# SparkFun_Qwiic_PIR.net
KiCad netlist of a schematic drawn in EAGLE
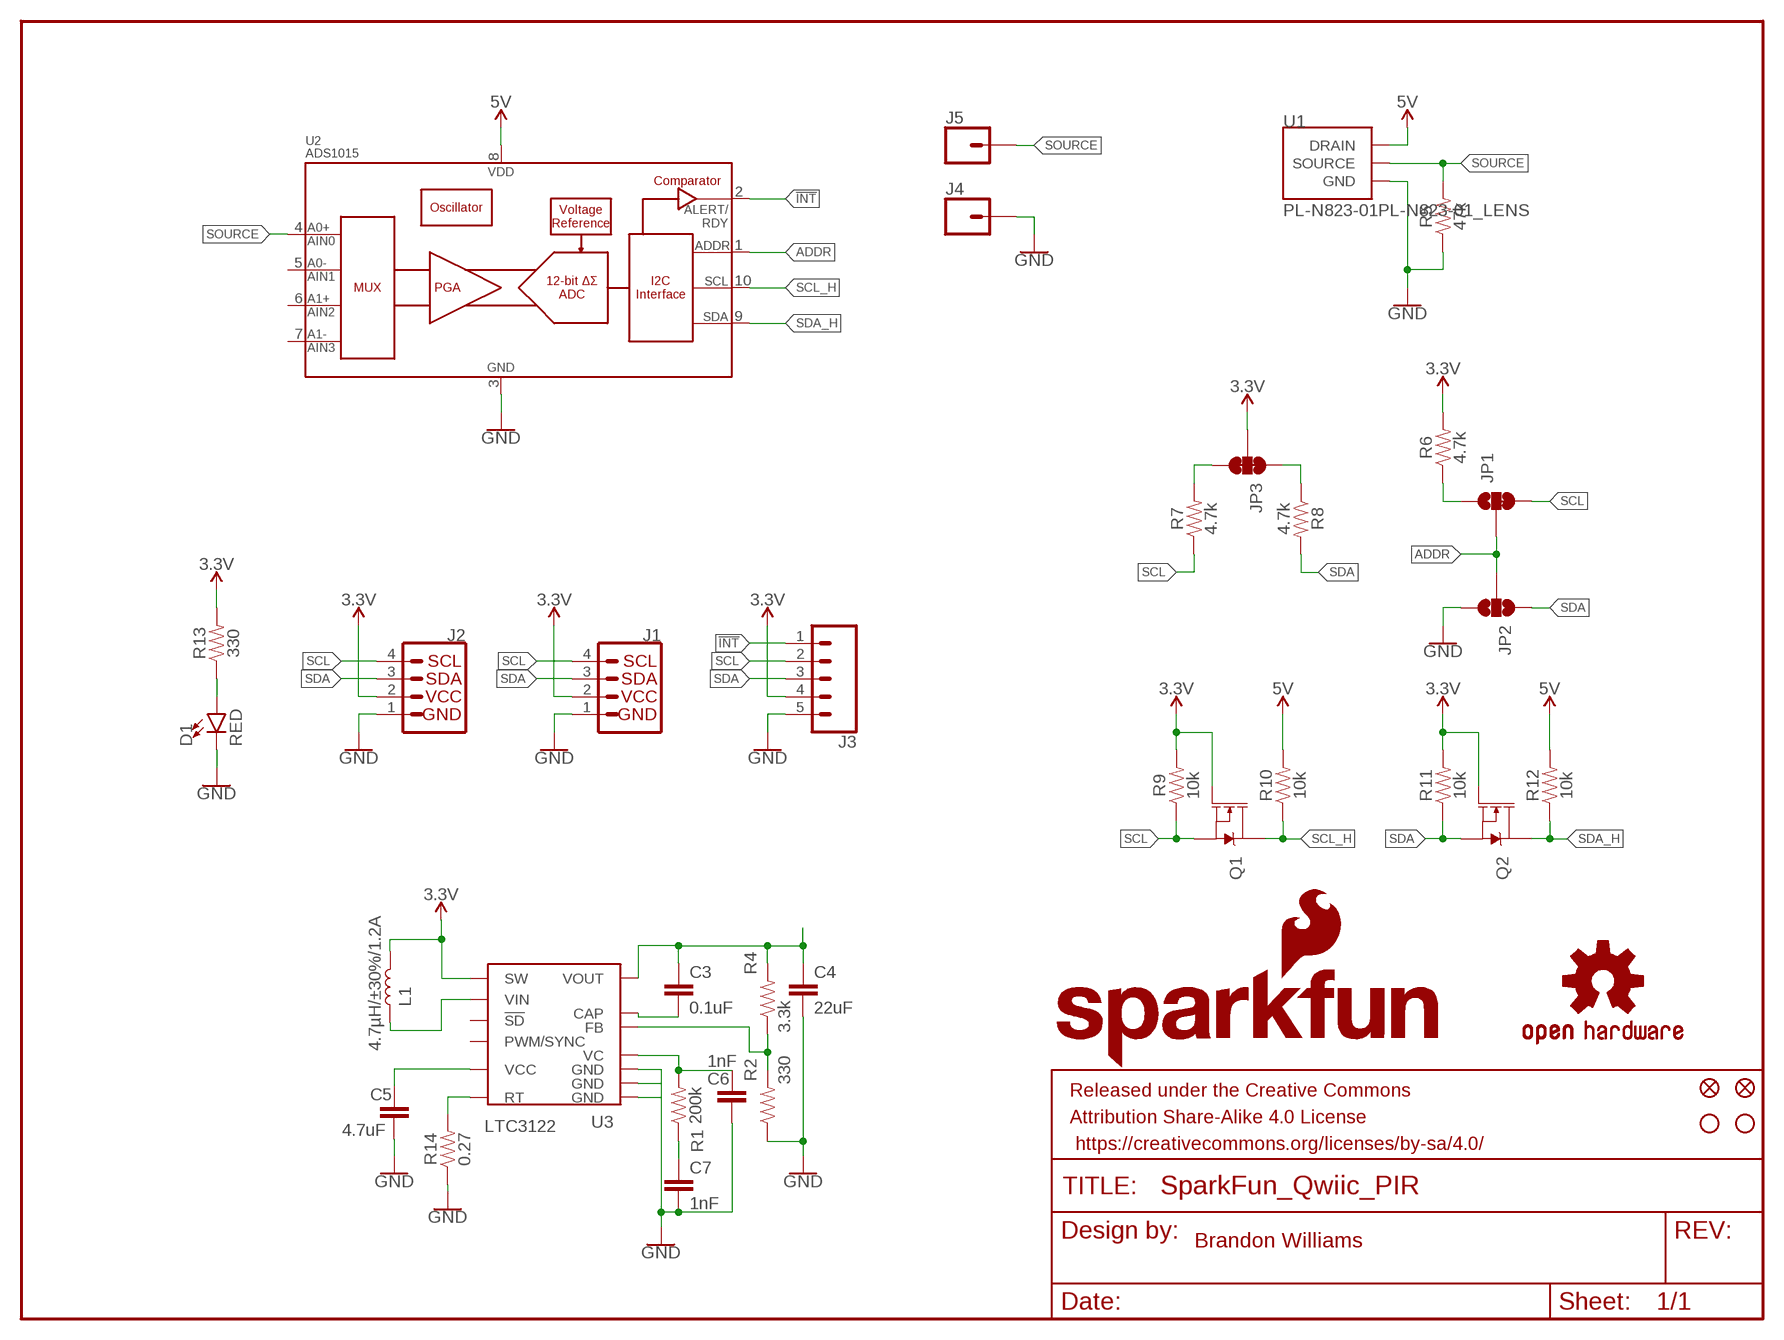
[diagram p0: schematic, sheet 1]

(export (version "E")
  (design (tool "Eeschema 10.0.6"))
  (components
    (comp (ref "C3")
      (value "0.1uF")
      (footprint "eagle-import:0603")
      (libsource (lib "eagle-import") (part "0.1UF-0603-25V-(+80/-20%)"))
    )
    (comp (ref "C4")
      (value "22uF")
      (footprint "eagle-import:0805")
      (libsource (lib "eagle-import") (part "22UF-0805-6.3V-20%"))
    )
    (comp (ref "C5")
      (value "4.7uF")
      (footprint "eagle-import:1206")
      (libsource (lib "eagle-import") (part "4.7UF-1206-16V-(+80/-20%)"))
    )
    (comp (ref "C6")
      (value "1nF")
      (footprint "eagle-import:0603")
      (libsource (lib "eagle-import") (part "1.0NF/1000PF-0603-50V-10%"))
    )
    (comp (ref "C7")
      (value "1nF")
      (footprint "eagle-import:0603")
      (libsource (lib "eagle-import") (part "1.0NF/1000PF-0603-50V-10%"))
    )
    (comp (ref "D1")
      (value "RED")
      (footprint "eagle-import:LED-0603")
      (libsource (lib "eagle-import") (part "LED-RED0603"))
    )
    (comp (ref "FD1")
      (value "FIDUCIAL0.2MM")
      (footprint "eagle-import:FIDUCIAL-0.2MM")
      (libsource (lib "eagle-import") (part "FIDUCIAL0.2MM"))
    )
    (comp (ref "FD2")
      (value "FIDUCIAL0.2MM")
      (footprint "eagle-import:FIDUCIAL-0.2MM")
      (libsource (lib "eagle-import") (part "FIDUCIAL0.2MM"))
    )
    (comp (ref "FRAME1")
      (value "FRAME-LETTERNO_PACKAGE")
      (footprint "eagle-import:DUMMY")
      (fields (field (name "DESIGNER") "Nobody"))
      (libsource (lib "eagle-import") (part "FRAME-LETTERNO_PACKAGE"))
    )
    (comp (ref "H1")
      (value "STAND-OFFTIGHT")
      (footprint "eagle-import:STAND-OFF-TIGHT")
      (libsource (lib "eagle-import") (part "STAND-OFFTIGHT"))
    )
    (comp (ref "H2")
      (value "STAND-OFFTIGHT")
      (footprint "eagle-import:STAND-OFF-TIGHT")
      (libsource (lib "eagle-import") (part "STAND-OFFTIGHT"))
    )
    (comp (ref "J1")
      (value "QWIIC_RIGHT_ANGLE")
      (footprint "eagle-import:JST04_1MM_RA")
      (libsource (lib "eagle-import") (part "QWIIC_CONNECTORJS-1MM"))
    )
    (comp (ref "J2")
      (value "QWIIC_RIGHT_ANGLE")
      (footprint "eagle-import:JST04_1MM_RA")
      (libsource (lib "eagle-import") (part "QWIIC_CONNECTORJS-1MM"))
    )
    (comp (ref "J3")
      (value "CONN_05NO_SILK")
      (footprint "eagle-import:1X05_NO_SILK")
      (libsource (lib "eagle-import") (part "CONN_05NO_SILK"))
    )
    (comp (ref "J4")
      (value "CONN_01PTH_NO_SILK_YES_STOP")
      (footprint "eagle-import:1X01_NO_SILK")
      (libsource (lib "eagle-import") (part "CONN_01PTH_NO_SILK_YES_STOP"))
    )
    (comp (ref "J5")
      (value "CONN_01PTH_NO_SILK_YES_STOP")
      (footprint "eagle-import:1X01_NO_SILK")
      (libsource (lib "eagle-import") (part "CONN_01PTH_NO_SILK_YES_STOP"))
    )
    (comp (ref "JP1")
      (value "JUMPER-SMT_3_1-NC_TRACE_SILK")
      (footprint "eagle-import:SMT-JUMPER_3_1-NC_TRACE_SILK")
      (libsource (lib "eagle-import") (part "JUMPER-SMT_3_1-NC_TRACE_SILK"))
    )
    (comp (ref "JP2")
      (value "JUMPER-SMT_3_NO_SILK")
      (footprint "eagle-import:SMT-JUMPER_3_NO_SILK")
      (libsource (lib "eagle-import") (part "JUMPER-SMT_3_NO_SILK"))
    )
    (comp (ref "JP3")
      (value "JUMPER-SMT_3_2-NC_TRACE_SILK")
      (footprint "eagle-import:SMT-JUMPER_3_2-NC_TRACE_SILK")
      (libsource (lib "eagle-import") (part "JUMPER-SMT_3_2-NC_TRACE_SILK"))
    )
    (comp (ref "L1")
      (value "4.7µH/±30%/1.2A")
      (footprint "eagle-import:INDUCTOR_4.7UH")
      (libsource (lib "eagle-import") (part "INDUCTOR-CDRH-4.7UH"))
    )
    (comp (ref "LOGO1")
      (value "OSHW-LOGOMINI")
      (footprint "eagle-import:OSHW-LOGO-MINI")
      (libsource (lib "eagle-import") (part "OSHW-LOGOMINI"))
    )
    (comp (ref "LOGO3")
      (value "SFE_LOGO_NAME_FLAME.2_INCH")
      (footprint "eagle-import:SFE_LOGO_NAME_FLAME_.2")
      (libsource (lib "eagle-import") (part "SFE_LOGO_NAME_FLAME.2_INCH"))
    )
    (comp (ref "Q1")
      (value "220mA/50V/3.5Ω")
      (footprint "eagle-import:SOT23-3")
      (libsource (lib "eagle-import") (part "MOSFET-NCH-BSS138"))
    )
    (comp (ref "Q2")
      (value "220mA/50V/3.5Ω")
      (footprint "eagle-import:SOT23-3")
      (libsource (lib "eagle-import") (part "MOSFET-NCH-BSS138"))
    )
    (comp (ref "R1")
      (value "200k")
      (footprint "eagle-import:0603")
      (libsource (lib "eagle-import") (part "200KOHM-0603-1/10W-1%"))
    )
    (comp (ref "R2")
      (value "330")
      (footprint "eagle-import:0603")
      (libsource (lib "eagle-import") (part "330OHM-0603-1/10W-1%"))
    )
    (comp (ref "R4")
      (value "3.3k")
      (footprint "eagle-import:0603")
      (libsource (lib "eagle-import") (part "3.3KOHM-0603-1/10W-1%"))
    )
    (comp (ref "R5")
      (value "47k")
      (footprint "eagle-import:0603")
      (libsource (lib "eagle-import") (part "47KOHM-0603-1/10W-1%"))
    )
    (comp (ref "R6")
      (value "4.7k")
      (footprint "eagle-import:0603")
      (libsource (lib "eagle-import") (part "4.7KOHM-0603-1/10W-1%"))
    )
    (comp (ref "R7")
      (value "4.7k")
      (footprint "eagle-import:0603")
      (libsource (lib "eagle-import") (part "4.7KOHM-0603-1/10W-1%"))
    )
    (comp (ref "R8")
      (value "4.7k")
      (footprint "eagle-import:0603")
      (libsource (lib "eagle-import") (part "4.7KOHM-0603-1/10W-1%"))
    )
    (comp (ref "R9")
      (value "10k")
      (footprint "eagle-import:0402-TIGHT")
      (libsource (lib "eagle-import") (part "10KOHM-0402T-1/16W-1%"))
    )
    (comp (ref "R10")
      (value "10k")
      (footprint "eagle-import:0402-TIGHT")
      (libsource (lib "eagle-import") (part "10KOHM-0402T-1/16W-1%"))
    )
    (comp (ref "R11")
      (value "10k")
      (footprint "eagle-import:0402-TIGHT")
      (libsource (lib "eagle-import") (part "10KOHM-0402T-1/16W-1%"))
    )
    (comp (ref "R12")
      (value "10k")
      (footprint "eagle-import:0402-TIGHT")
      (libsource (lib "eagle-import") (part "10KOHM-0402T-1/16W-1%"))
    )
    (comp (ref "R13")
      (value "330")
      (footprint "eagle-import:0603")
      (libsource (lib "eagle-import") (part "330OHM-0603-1/10W-1%"))
    )
    (comp (ref "R14")
      (value "0.27")
      (footprint "eagle-import:0603")
      (libsource (lib "eagle-import") (part "0.27OHM-0603-1/10W-1%"))
    )
    (comp (ref "U1")
      (value "PL-N823-01PL-N823-01_LENS")
      (footprint "eagle-import:PL-N823-01_LENS")
      (libsource (lib "eagle-import") (part "PL-N823-01PL-N823-01_LENS"))
    )
    (comp (ref "U2")
      (value "ADS1015")
      (footprint "eagle-import:MSOP10")
      (libsource (lib "eagle-import") (part "ADS1015"))
    )
    (comp (ref "U3")
      (value "LTC3122")
      (footprint "eagle-import:LTC3122EDE#PBF")
      (libsource (lib "eagle-import") (part "LTC3122"))
    )
  )
  (nets
    (net (code "1") (name "/~{INT}") (class "Default")
      (node (ref "J3") (pin "1") (pinfunction "1_1") (pintype "passive"))
      (node (ref "U2") (pin "2") (pinfunction "ALERT/RDY_2") (pintype "bidirectional"))
    )
    (net (code "2") (name "3.3V") (class "Default")
      (node (ref "J1") (pin "2") (pinfunction "2_2") (pintype "power_in"))
      (node (ref "J2") (pin "2") (pinfunction "2_2") (pintype "power_in"))
      (node (ref "J3") (pin "4") (pinfunction "4_4") (pintype "passive"))
      (node (ref "JP3") (pin "2") (pinfunction "2_2") (pintype "passive"))
      (node (ref "L1") (pin "P$2") (pinfunction "2_P$2") (pintype "passive"))
      (node (ref "Q1") (pin "1") (pinfunction "G_1") (pintype "bidirectional"))
      (node (ref "Q2") (pin "1") (pinfunction "G_1") (pintype "bidirectional"))
      (node (ref "R11") (pin "2") (pinfunction "2_2") (pintype "passive"))
      (node (ref "R13") (pin "2") (pinfunction "2_2") (pintype "passive"))
      (node (ref "R6") (pin "2") (pinfunction "2_2") (pintype "passive"))
      (node (ref "R9") (pin "2") (pinfunction "2_2") (pintype "passive"))
      (node (ref "U3") (pin "P$1") (pinfunction "SW_P$1") (pintype "input"))
    )
    (net (code "3") (name "5V") (class "Default")
      (node (ref "R10") (pin "2") (pinfunction "2_2") (pintype "passive"))
      (node (ref "R12") (pin "2") (pinfunction "2_2") (pintype "passive"))
      (node (ref "U1") (pin "DRAIN") (pinfunction "DRAIN_DRAIN") (pintype "input"))
      (node (ref "U2") (pin "8") (pinfunction "VDD_8") (pintype "bidirectional"))
    )
    (net (code "4") (name "ADDR") (class "Default")
      (node (ref "JP1") (pin "2") (pinfunction "2_2") (pintype "passive"))
      (node (ref "JP2") (pin "2") (pinfunction "2_2") (pintype "passive"))
      (node (ref "U2") (pin "1") (pinfunction "ADDR_1") (pintype "bidirectional"))
    )
    (net (code "5") (name "GND") (class "Default")
      (node (ref "C4") (pin "2") (pinfunction "2_2") (pintype "passive"))
      (node (ref "C5") (pin "2") (pinfunction "2_2") (pintype "passive"))
      (node (ref "C6") (pin "2") (pinfunction "2_2") (pintype "passive"))
      (node (ref "C7") (pin "2") (pinfunction "2_2") (pintype "passive"))
      (node (ref "D1") (pin "C") (pinfunction "C_C") (pintype "passive"))
      (node (ref "J1") (pin "1") (pinfunction "1_1") (pintype "power_in"))
      (node (ref "J2") (pin "1") (pinfunction "1_1") (pintype "power_in"))
      (node (ref "J3") (pin "5") (pinfunction "5_5") (pintype "passive"))
      (node (ref "J4") (pin "1") (pinfunction "1_1") (pintype "passive"))
      (node (ref "JP2") (pin "3") (pinfunction "3_3") (pintype "passive"))
      (node (ref "R14") (pin "1") (pinfunction "1_1") (pintype "passive"))
      (node (ref "R2") (pin "1") (pinfunction "1_1") (pintype "passive"))
      (node (ref "R5") (pin "1") (pinfunction "1_1") (pintype "passive"))
      (node (ref "U1") (pin "GND@1") (pinfunction "GND_GND@1") (pintype "power_in"))
      (node (ref "U1") (pin "GND@2") (pinfunction "GND_GND@2") (pintype "power_in"))
      (node (ref "U2") (pin "3") (pinfunction "VSS_3") (pintype "bidirectional"))
      (node (ref "U3") (pin "P$10") (pinfunction "GND_P$10") (pintype "power_in"))
      (node (ref "U3") (pin "P$13") (pinfunction "GND_P$13") (pintype "power_in"))
      (node (ref "U3") (pin "P$2") (pinfunction "GND_P$2") (pintype "power_in"))
    )
    (net (code "6") (name "Net-(C7-Pad1)") (class "Default")
      (node (ref "C7") (pin "1") (pinfunction "1_1") (pintype "passive"))
      (node (ref "R1") (pin "1") (pinfunction "1_1") (pintype "passive"))
    )
    (net (code "7") (name "Net-(D1-PadA)") (class "Default")
      (node (ref "D1") (pin "A") (pinfunction "A_A") (pintype "passive"))
      (node (ref "R13") (pin "1") (pinfunction "1_1") (pintype "passive"))
    )
    (net (code "8") (name "Net-(JP1-Pad1)") (class "Default")
      (node (ref "JP1") (pin "1") (pinfunction "1_1") (pintype "passive"))
      (node (ref "R6") (pin "1") (pinfunction "1_1") (pintype "passive"))
    )
    (net (code "9") (name "Net-(JP3-Pad1)") (class "Default")
      (node (ref "JP3") (pin "1") (pinfunction "1_1") (pintype "passive"))
      (node (ref "R8") (pin "1") (pinfunction "1_1") (pintype "passive"))
    )
    (net (code "10") (name "Net-(JP3-Pad3)") (class "Default")
      (node (ref "JP3") (pin "3") (pinfunction "3_3") (pintype "passive"))
      (node (ref "R7") (pin "2") (pinfunction "2_2") (pintype "passive"))
    )
    (net (code "11") (name "Net-(L1-1)") (class "Default")
      (node (ref "L1") (pin "P$1") (pinfunction "1_P$1") (pintype "passive"))
      (node (ref "U3") (pin "P$3") (pinfunction "VIN_P$3") (pintype "power_in"))
    )
    (net (code "12") (name "Net-(U3-CAP)") (class "Default")
      (node (ref "C3") (pin "2") (pinfunction "2_2") (pintype "passive"))
      (node (ref "U3") (pin "P$12") (pinfunction "CAP_P$12") (pintype "passive"))
    )
    (net (code "13") (name "Net-(U3-FB)") (class "Default")
      (node (ref "R2") (pin "2") (pinfunction "2_2") (pintype "passive"))
      (node (ref "R4") (pin "1") (pinfunction "1_1") (pintype "passive"))
      (node (ref "U3") (pin "P$8") (pinfunction "FB_P$8") (pintype "bidirectional"))
    )
    (net (code "14") (name "Net-(U3-RT)") (class "Default")
      (node (ref "R14") (pin "2") (pinfunction "2_2") (pintype "passive"))
      (node (ref "U3") (pin "P$6") (pinfunction "RT_P$6") (pintype "bidirectional"))
    )
    (net (code "15") (name "Net-(U3-VC)") (class "Default")
      (node (ref "C6") (pin "1") (pinfunction "1_1") (pintype "passive"))
      (node (ref "R1") (pin "2") (pinfunction "2_2") (pintype "passive"))
      (node (ref "U3") (pin "P$7") (pinfunction "VC_P$7") (pintype "bidirectional"))
    )
    (net (code "16") (name "Net-(U3-VCC)") (class "Default")
      (node (ref "C5") (pin "1") (pinfunction "1_1") (pintype "passive"))
      (node (ref "U3") (pin "P$5") (pinfunction "VCC_P$5") (pintype "bidirectional"))
    )
    (net (code "17") (name "Net-(U3-VOUT)") (class "Default")
      (node (ref "C3") (pin "1") (pinfunction "1_1") (pintype "passive"))
      (node (ref "C4") (pin "1") (pinfunction "1_1") (pintype "passive"))
      (node (ref "R4") (pin "2") (pinfunction "2_2") (pintype "passive"))
      (node (ref "U3") (pin "P$11") (pinfunction "VOUT_P$11") (pintype "output"))
    )
    (net (code "18") (name "SCL") (class "Default")
      (node (ref "J1") (pin "4") (pinfunction "4_4") (pintype "passive"))
      (node (ref "J2") (pin "4") (pinfunction "4_4") (pintype "passive"))
      (node (ref "J3") (pin "2") (pinfunction "2_2") (pintype "passive"))
      (node (ref "JP1") (pin "3") (pinfunction "3_3") (pintype "passive"))
      (node (ref "Q1") (pin "2") (pinfunction "S_2") (pintype "bidirectional"))
      (node (ref "R7") (pin "1") (pinfunction "1_1") (pintype "passive"))
      (node (ref "R9") (pin "1") (pinfunction "1_1") (pintype "passive"))
    )
    (net (code "19") (name "SCL_H") (class "Default")
      (node (ref "Q1") (pin "3") (pinfunction "D_3") (pintype "bidirectional"))
      (node (ref "R10") (pin "1") (pinfunction "1_1") (pintype "passive"))
      (node (ref "U2") (pin "10") (pinfunction "SCL_10") (pintype "bidirectional"))
    )
    (net (code "20") (name "SDA") (class "Default")
      (node (ref "J1") (pin "3") (pinfunction "3_3") (pintype "passive"))
      (node (ref "J2") (pin "3") (pinfunction "3_3") (pintype "passive"))
      (node (ref "J3") (pin "3") (pinfunction "3_3") (pintype "passive"))
      (node (ref "JP2") (pin "1") (pinfunction "1_1") (pintype "passive"))
      (node (ref "Q2") (pin "2") (pinfunction "S_2") (pintype "bidirectional"))
      (node (ref "R11") (pin "1") (pinfunction "1_1") (pintype "passive"))
      (node (ref "R8") (pin "2") (pinfunction "2_2") (pintype "passive"))
    )
    (net (code "21") (name "SDA_H") (class "Default")
      (node (ref "Q2") (pin "3") (pinfunction "D_3") (pintype "bidirectional"))
      (node (ref "R12") (pin "1") (pinfunction "1_1") (pintype "passive"))
      (node (ref "U2") (pin "9") (pinfunction "SDA_9") (pintype "bidirectional"))
    )
    (net (code "22") (name "SOURCE") (class "Default")
      (node (ref "J5") (pin "1") (pinfunction "1_1") (pintype "passive"))
      (node (ref "R5") (pin "2") (pinfunction "2_2") (pintype "passive"))
      (node (ref "U1") (pin "SOURCE") (pinfunction "SOURCE_SOURCE") (pintype "output"))
      (node (ref "U2") (pin "4") (pinfunction "AIN0_4") (pintype "bidirectional"))
    )
    (net (code "23") (name "unconnected-(U2-AIN1-Pad5)") (class "Default")
      (node (ref "U2") (pin "5") (pinfunction "AIN1_5") (pintype "bidirectional"))
    )
    (net (code "24") (name "unconnected-(U2-AIN2-Pad6)") (class "Default")
      (node (ref "U2") (pin "6") (pinfunction "AIN2_6") (pintype "bidirectional"))
    )
    (net (code "25") (name "unconnected-(U2-AIN3-Pad7)") (class "Default")
      (node (ref "U2") (pin "7") (pinfunction "AIN3_7") (pintype "bidirectional"))
    )
    (net (code "26") (name "unconnected-(U3-PWM{slash}SYNC-PadP$4)") (class "Default")
      (node (ref "U3") (pin "P$4") (pinfunction "PWM/SYNC_P$4") (pintype "input"))
    )
    (net (code "27") (name "unconnected-(U3-~{SD}-PadP$9)") (class "Default")
      (node (ref "U3") (pin "P$9") (pinfunction "~{SD}_P$9") (pintype "input"))
    )
  )
)
